# ADS7046_v6.net
KiCad netlist of a schematic drawn in EAGLE
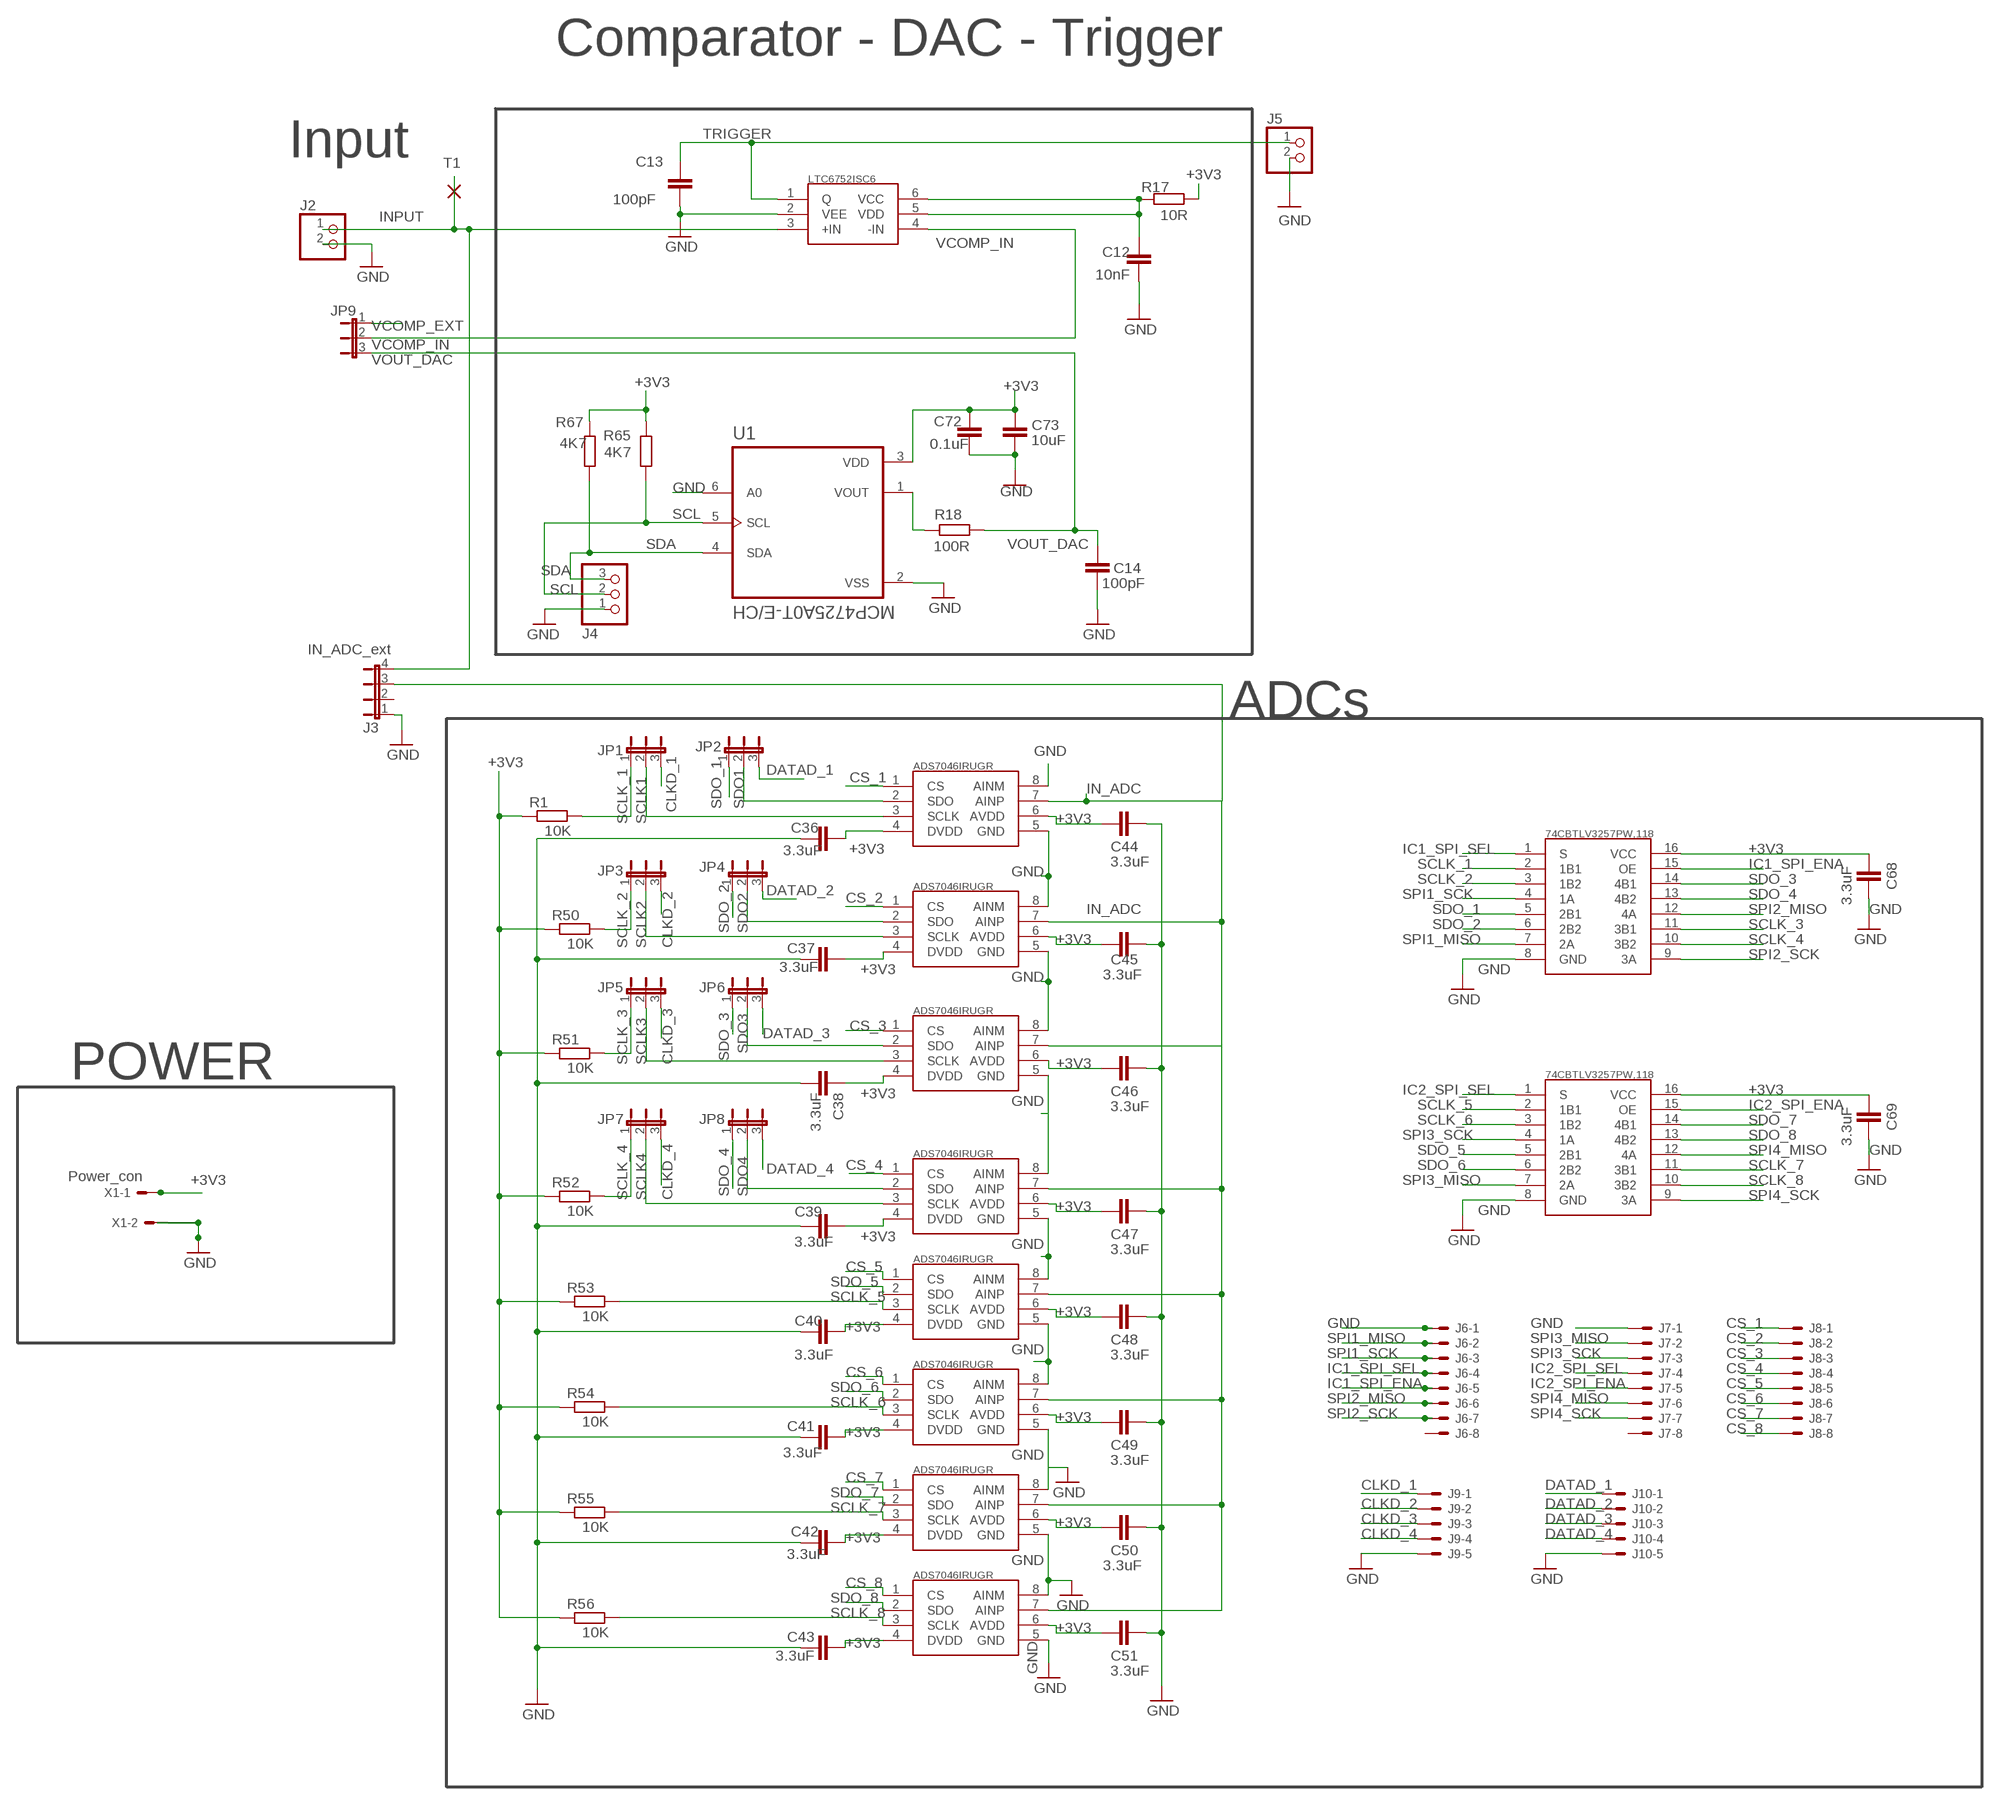
[diagram p0: schematic, sheet 1]

(export (version "E")
  (design (tool "Eeschema 10.0.6"))
  (components
    (comp (ref "C12")
      (value "10nF")
      (footprint "eagle-import:C1206")
      (libsource (lib "eagle-import") (part "C-EUC1206"))
    )
    (comp (ref "C13")
      (value "100pF")
      (footprint "eagle-import:C1206")
      (libsource (lib "eagle-import") (part "C-EUC1206"))
    )
    (comp (ref "C14")
      (value "100pF")
      (footprint "eagle-import:C1206")
      (libsource (lib "eagle-import") (part "C-EUC1206"))
    )
    (comp (ref "C36")
      (value "3.3uF")
      (footprint "eagle-import:C0805")
      (libsource (lib "eagle-import") (part "C-EUC0805"))
    )
    (comp (ref "C37")
      (value "3.3uF")
      (footprint "eagle-import:C0805")
      (libsource (lib "eagle-import") (part "C-EUC0805"))
    )
    (comp (ref "C38")
      (value "3.3uF")
      (footprint "eagle-import:C0805")
      (libsource (lib "eagle-import") (part "C-EUC0805"))
    )
    (comp (ref "C39")
      (value "3.3uF")
      (footprint "eagle-import:C0805")
      (libsource (lib "eagle-import") (part "C-EUC0805"))
    )
    (comp (ref "C40")
      (value "3.3uF")
      (footprint "eagle-import:C0805")
      (libsource (lib "eagle-import") (part "C-EUC0805"))
    )
    (comp (ref "C41")
      (value "3.3uF")
      (footprint "eagle-import:C0805")
      (libsource (lib "eagle-import") (part "C-EUC0805"))
    )
    (comp (ref "C42")
      (value "3.3uF")
      (footprint "eagle-import:C0805")
      (libsource (lib "eagle-import") (part "C-EUC0805"))
    )
    (comp (ref "C43")
      (value "3.3uF")
      (footprint "eagle-import:C0805")
      (libsource (lib "eagle-import") (part "C-EUC0805"))
    )
    (comp (ref "C44")
      (value "3.3uF")
      (footprint "eagle-import:C0805")
      (libsource (lib "eagle-import") (part "C-EUC0805"))
    )
    (comp (ref "C45")
      (value "3.3uF")
      (footprint "eagle-import:C0805")
      (libsource (lib "eagle-import") (part "C-EUC0805"))
    )
    (comp (ref "C46")
      (value "3.3uF")
      (footprint "eagle-import:C0805")
      (libsource (lib "eagle-import") (part "C-EUC0805"))
    )
    (comp (ref "C47")
      (value "3.3uF")
      (footprint "eagle-import:C0805")
      (libsource (lib "eagle-import") (part "C-EUC0805"))
    )
    (comp (ref "C48")
      (value "3.3uF")
      (footprint "eagle-import:C0805")
      (libsource (lib "eagle-import") (part "C-EUC0805"))
    )
    (comp (ref "C49")
      (value "3.3uF")
      (footprint "eagle-import:C0805")
      (libsource (lib "eagle-import") (part "C-EUC0805"))
    )
    (comp (ref "C50")
      (value "3.3uF")
      (footprint "eagle-import:C0805")
      (libsource (lib "eagle-import") (part "C-EUC0805"))
    )
    (comp (ref "C51")
      (value "3.3uF")
      (footprint "eagle-import:C0805")
      (libsource (lib "eagle-import") (part "C-EUC0805"))
    )
    (comp (ref "C68")
      (value "3.3uF")
      (footprint "eagle-import:C0805")
      (libsource (lib "eagle-import") (part "C-EUC0805"))
    )
    (comp (ref "C69")
      (value "3.3uF")
      (footprint "eagle-import:C0805")
      (libsource (lib "eagle-import") (part "C-EUC0805"))
    )
    (comp (ref "C72")
      (value "0.1uF")
      (footprint "eagle-import:C0805")
      (libsource (lib "eagle-import") (part "C-EUC0805"))
    )
    (comp (ref "C73")
      (value "10uF")
      (footprint "eagle-import:C0805")
      (libsource (lib "eagle-import") (part "C-EUC0805"))
    )
    (comp (ref "J2")
      (value "PINHD-1X2")
      (footprint "eagle-import:1X02")
      (libsource (lib "eagle-import") (part "PINHD-1X2"))
    )
    (comp (ref "J3")
      (value "IN_ADC_ext")
      (footprint "eagle-import:JP4")
      (libsource (lib "eagle-import") (part "JP4E"))
    )
    (comp (ref "J4")
      (value "PINHD-1X3")
      (footprint "eagle-import:1X03")
      (libsource (lib "eagle-import") (part "PINHD-1X3"))
    )
    (comp (ref "J5")
      (value "PINHD-1X2")
      (footprint "eagle-import:1X02")
      (libsource (lib "eagle-import") (part "PINHD-1X2"))
    )
    (comp (ref "J6")
      (value "22-27-2081-08")
      (footprint "eagle-import:6410-08")
      (fields (field (name "MF") "MOLEX"))
      (libsource (lib "eagle-import") (part "22-?-0827-2081"))
    )
    (comp (ref "J7")
      (value "22-27-2081-08")
      (footprint "eagle-import:6410-08")
      (fields (field (name "MF") "MOLEX"))
      (libsource (lib "eagle-import") (part "22-?-0827-2081"))
    )
    (comp (ref "J8")
      (value "22-27-2081-08")
      (footprint "eagle-import:6410-08")
      (fields (field (name "MF") "MOLEX"))
      (libsource (lib "eagle-import") (part "22-?-0827-2081"))
    )
    (comp (ref "J9")
      (value "22-27-2051-05")
      (footprint "eagle-import:6410-05")
      (fields (field (name "MF") "MOLEX"))
      (libsource (lib "eagle-import") (part "22-?-0527-2051"))
    )
    (comp (ref "J10")
      (value "22-27-2051-05")
      (footprint "eagle-import:6410-05")
      (fields (field (name "MF") "MOLEX"))
      (libsource (lib "eagle-import") (part "22-?-0527-2051"))
    )
    (comp (ref "JP1")
      (value "JP2E")
      (footprint "eagle-import:JP2")
      (libsource (lib "eagle-import") (part "JP2E"))
    )
    (comp (ref "JP2")
      (value "JP2E")
      (footprint "eagle-import:JP2")
      (libsource (lib "eagle-import") (part "JP2E"))
    )
    (comp (ref "JP3")
      (value "JP2E")
      (footprint "eagle-import:JP2")
      (libsource (lib "eagle-import") (part "JP2E"))
    )
    (comp (ref "JP4")
      (value "JP2E")
      (footprint "eagle-import:JP2")
      (libsource (lib "eagle-import") (part "JP2E"))
    )
    (comp (ref "JP5")
      (value "JP2E")
      (footprint "eagle-import:JP2")
      (libsource (lib "eagle-import") (part "JP2E"))
    )
    (comp (ref "JP6")
      (value "JP2E")
      (footprint "eagle-import:JP2")
      (libsource (lib "eagle-import") (part "JP2E"))
    )
    (comp (ref "JP7")
      (value "JP2E")
      (footprint "eagle-import:JP2")
      (libsource (lib "eagle-import") (part "JP2E"))
    )
    (comp (ref "JP8")
      (value "JP2E")
      (footprint "eagle-import:JP2")
      (libsource (lib "eagle-import") (part "JP2E"))
    )
    (comp (ref "JP9")
      (value "JP2E")
      (footprint "eagle-import:JP2")
      (libsource (lib "eagle-import") (part "JP2E"))
    )
    (comp (ref "R1")
      (value "10K")
      (footprint "eagle-import:R0805")
      (libsource (lib "eagle-import") (part "R-EU_R0805"))
    )
    (comp (ref "R17")
      (value "10R")
      (footprint "eagle-import:R1206")
      (libsource (lib "eagle-import") (part "R-EU_R1206"))
    )
    (comp (ref "R18")
      (value "100R")
      (footprint "eagle-import:R1206")
      (libsource (lib "eagle-import") (part "R-EU_R1206"))
    )
    (comp (ref "R50")
      (value "10K")
      (footprint "eagle-import:R0805")
      (libsource (lib "eagle-import") (part "R-EU_R0805"))
    )
    (comp (ref "R51")
      (value "10K")
      (footprint "eagle-import:R0805")
      (libsource (lib "eagle-import") (part "R-EU_R0805"))
    )
    (comp (ref "R52")
      (value "10K")
      (footprint "eagle-import:R0805")
      (libsource (lib "eagle-import") (part "R-EU_R0805"))
    )
    (comp (ref "R53")
      (value "10K")
      (footprint "eagle-import:R0805")
      (libsource (lib "eagle-import") (part "R-EU_R0805"))
    )
    (comp (ref "R54")
      (value "10K")
      (footprint "eagle-import:R0805")
      (libsource (lib "eagle-import") (part "R-EU_R0805"))
    )
    (comp (ref "R55")
      (value "10K")
      (footprint "eagle-import:R0805")
      (libsource (lib "eagle-import") (part "R-EU_R0805"))
    )
    (comp (ref "R56")
      (value "10K")
      (footprint "eagle-import:R0805")
      (libsource (lib "eagle-import") (part "R-EU_R0805"))
    )
    (comp (ref "R65")
      (value "4K7")
      (footprint "eagle-import:R0805")
      (libsource (lib "eagle-import") (part "R-EU_R0805"))
    )
    (comp (ref "R67")
      (value "4K7")
      (footprint "eagle-import:R0805")
      (libsource (lib "eagle-import") (part "R-EU_R0805"))
    )
    (comp (ref "T1")
      (value "WIREPADSMD1,27-254")
      (footprint "eagle-import:SMD1,27-2,54")
      (libsource (lib "eagle-import") (part "WIREPADSMD1,27-254"))
    )
    (comp (ref "U$2")
      (value "LTC6752ISC6")
      (footprint "eagle-import:LTC6752ISC6")
      (libsource (lib "eagle-import") (part "LTC6752ISC6"))
    )
    (comp (ref "U$12")
      (value "ADS7046IRUGR")
      (footprint "eagle-import:ADS7046IRUGR")
      (libsource (lib "eagle-import") (part "ADS7046IRUGR"))
    )
    (comp (ref "U$13")
      (value "ADS7046IRUGR")
      (footprint "eagle-import:ADS7046IRUGR")
      (libsource (lib "eagle-import") (part "ADS7046IRUGR"))
    )
    (comp (ref "U$14")
      (value "ADS7046IRUGR")
      (footprint "eagle-import:ADS7046IRUGR")
      (libsource (lib "eagle-import") (part "ADS7046IRUGR"))
    )
    (comp (ref "U$15")
      (value "ADS7046IRUGR")
      (footprint "eagle-import:ADS7046IRUGR")
      (libsource (lib "eagle-import") (part "ADS7046IRUGR"))
    )
    (comp (ref "U$16")
      (value "ADS7046IRUGR")
      (footprint "eagle-import:ADS7046IRUGR")
      (libsource (lib "eagle-import") (part "ADS7046IRUGR"))
    )
    (comp (ref "U$17")
      (value "ADS7046IRUGR")
      (footprint "eagle-import:ADS7046IRUGR")
      (libsource (lib "eagle-import") (part "ADS7046IRUGR"))
    )
    (comp (ref "U$18")
      (value "ADS7046IRUGR")
      (footprint "eagle-import:ADS7046IRUGR")
      (libsource (lib "eagle-import") (part "ADS7046IRUGR"))
    )
    (comp (ref "U$19")
      (value "ADS7046IRUGR")
      (footprint "eagle-import:ADS7046IRUGR")
      (libsource (lib "eagle-import") (part "ADS7046IRUGR"))
    )
    (comp (ref "U$28")
      (value "74CBTLV3257PW,118")
      (footprint "eagle-import:TSSOP16")
      (libsource (lib "eagle-import") (part "74CBTLV3257PW,118"))
    )
    (comp (ref "U$29")
      (value "74CBTLV3257PW,118")
      (footprint "eagle-import:TSSOP16")
      (libsource (lib "eagle-import") (part "74CBTLV3257PW,118"))
    )
    (comp (ref "U1")
      (value "MCP4725A0T-E/CH")
      (footprint "eagle-import:SOT95P270X145-6N")
      (fields (field (name "MF") "Microchip"))
      (libsource (lib "eagle-import") (part "MCP4725A0T-E/CH"))
    )
    (comp (ref "X1")
      (value "Power_con")
      (footprint "eagle-import:22-23-2021")
      (fields (field (name "MF") "MOLEX") (field (name "MPN") "22-23-2021"))
      (libsource (lib "eagle-import") (part "22-23-2021"))
    )
  )
  (nets
    (net (code "1") (name "/+3V3") (class "Default")
      (node (ref "C36") (pin "1") (pinfunction "1_1") (pintype "passive"))
      (node (ref "C37") (pin "1") (pinfunction "1_1") (pintype "passive"))
      (node (ref "C38") (pin "1") (pinfunction "1_1") (pintype "passive"))
      (node (ref "C39") (pin "1") (pinfunction "1_1") (pintype "passive"))
      (node (ref "C40") (pin "1") (pinfunction "1_1") (pintype "passive"))
      (node (ref "C41") (pin "1") (pinfunction "1_1") (pintype "passive"))
      (node (ref "C42") (pin "1") (pinfunction "1_1") (pintype "passive"))
      (node (ref "C43") (pin "1") (pinfunction "1_1") (pintype "passive"))
      (node (ref "C44") (pin "2") (pinfunction "2_2") (pintype "passive"))
      (node (ref "C45") (pin "2") (pinfunction "2_2") (pintype "passive"))
      (node (ref "C46") (pin "2") (pinfunction "2_2") (pintype "passive"))
      (node (ref "C47") (pin "2") (pinfunction "2_2") (pintype "passive"))
      (node (ref "C48") (pin "2") (pinfunction "2_2") (pintype "passive"))
      (node (ref "C49") (pin "2") (pinfunction "2_2") (pintype "passive"))
      (node (ref "C50") (pin "2") (pinfunction "2_2") (pintype "passive"))
      (node (ref "C51") (pin "2") (pinfunction "2_2") (pintype "passive"))
      (node (ref "C68") (pin "1") (pinfunction "1_1") (pintype "passive"))
      (node (ref "C69") (pin "1") (pinfunction "1_1") (pintype "passive"))
      (node (ref "C72") (pin "1") (pinfunction "1_1") (pintype "passive"))
      (node (ref "C73") (pin "1") (pinfunction "1_1") (pintype "passive"))
      (node (ref "R1") (pin "1") (pinfunction "1_1") (pintype "passive"))
      (node (ref "R17") (pin "1") (pinfunction "1_1") (pintype "passive"))
      (node (ref "R50") (pin "1") (pinfunction "1_1") (pintype "passive"))
      (node (ref "R51") (pin "1") (pinfunction "1_1") (pintype "passive"))
      (node (ref "R52") (pin "1") (pinfunction "1_1") (pintype "passive"))
      (node (ref "R53") (pin "1") (pinfunction "1_1") (pintype "passive"))
      (node (ref "R54") (pin "1") (pinfunction "1_1") (pintype "passive"))
      (node (ref "R55") (pin "1") (pinfunction "1_1") (pintype "passive"))
      (node (ref "R56") (pin "1") (pinfunction "1_1") (pintype "passive"))
      (node (ref "R65") (pin "2") (pinfunction "2_2") (pintype "passive"))
      (node (ref "R67") (pin "1") (pinfunction "1_1") (pintype "passive"))
      (node (ref "U$12") (pin "4") (pinfunction "DVDD_4") (pintype "bidirectional"))
      (node (ref "U$12") (pin "6") (pinfunction "AVDD_6") (pintype "bidirectional"))
      (node (ref "U$13") (pin "4") (pinfunction "DVDD_4") (pintype "bidirectional"))
      (node (ref "U$13") (pin "6") (pinfunction "AVDD_6") (pintype "bidirectional"))
      (node (ref "U$14") (pin "4") (pinfunction "DVDD_4") (pintype "bidirectional"))
      (node (ref "U$14") (pin "6") (pinfunction "AVDD_6") (pintype "bidirectional"))
      (node (ref "U$15") (pin "4") (pinfunction "DVDD_4") (pintype "bidirectional"))
      (node (ref "U$15") (pin "6") (pinfunction "AVDD_6") (pintype "bidirectional"))
      (node (ref "U$16") (pin "4") (pinfunction "DVDD_4") (pintype "bidirectional"))
      (node (ref "U$16") (pin "6") (pinfunction "AVDD_6") (pintype "bidirectional"))
      (node (ref "U$17") (pin "4") (pinfunction "DVDD_4") (pintype "bidirectional"))
      (node (ref "U$17") (pin "6") (pinfunction "AVDD_6") (pintype "bidirectional"))
      (node (ref "U$18") (pin "4") (pinfunction "DVDD_4") (pintype "bidirectional"))
      (node (ref "U$18") (pin "6") (pinfunction "AVDD_6") (pintype "bidirectional"))
      (node (ref "U$19") (pin "4") (pinfunction "DVDD_4") (pintype "bidirectional"))
      (node (ref "U$19") (pin "6") (pinfunction "AVDD_6") (pintype "bidirectional"))
      (node (ref "U$28") (pin "16") (pinfunction "VCC_16") (pintype "bidirectional"))
      (node (ref "U$29") (pin "16") (pinfunction "VCC_16") (pintype "bidirectional"))
      (node (ref "U1") (pin "3") (pinfunction "VDD_3") (pintype "power_in"))
      (node (ref "X1") (pin "1") (pinfunction "S_1") (pintype "passive"))
    )
    (net (code "2") (name "/CLKD_1") (class "Default")
      (node (ref "J9") (pin "1") (pinfunction "S_1") (pintype "passive"))
      (node (ref "JP1") (pin "3") (pinfunction "3_3") (pintype "passive"))
    )
    (net (code "3") (name "/CLKD_2") (class "Default")
      (node (ref "J9") (pin "2") (pinfunction "S_2") (pintype "passive"))
      (node (ref "JP3") (pin "3") (pinfunction "3_3") (pintype "passive"))
    )
    (net (code "4") (name "/CLKD_3") (class "Default")
      (node (ref "J9") (pin "3") (pinfunction "S_3") (pintype "passive"))
      (node (ref "JP5") (pin "3") (pinfunction "3_3") (pintype "passive"))
    )
    (net (code "5") (name "/CLKD_4") (class "Default")
      (node (ref "J9") (pin "4") (pinfunction "S_4") (pintype "passive"))
      (node (ref "JP7") (pin "3") (pinfunction "3_3") (pintype "passive"))
    )
    (net (code "6") (name "/CS_1") (class "Default")
      (node (ref "J8") (pin "1") (pinfunction "S_1") (pintype "passive"))
      (node (ref "U$12") (pin "1") (pinfunction "CS_1") (pintype "bidirectional"))
    )
    (net (code "7") (name "/CS_2") (class "Default")
      (node (ref "J8") (pin "2") (pinfunction "S_2") (pintype "passive"))
      (node (ref "U$13") (pin "1") (pinfunction "CS_1") (pintype "bidirectional"))
    )
    (net (code "8") (name "/CS_3") (class "Default")
      (node (ref "J8") (pin "3") (pinfunction "S_3") (pintype "passive"))
      (node (ref "U$14") (pin "1") (pinfunction "CS_1") (pintype "bidirectional"))
    )
    (net (code "9") (name "/CS_4") (class "Default")
      (node (ref "J8") (pin "4") (pinfunction "S_4") (pintype "passive"))
      (node (ref "U$15") (pin "1") (pinfunction "CS_1") (pintype "bidirectional"))
    )
    (net (code "10") (name "/CS_5") (class "Default")
      (node (ref "J8") (pin "5") (pinfunction "S_5") (pintype "passive"))
      (node (ref "U$16") (pin "1") (pinfunction "CS_1") (pintype "bidirectional"))
    )
    (net (code "11") (name "/CS_6") (class "Default")
      (node (ref "J8") (pin "6") (pinfunction "S_6") (pintype "passive"))
      (node (ref "U$17") (pin "1") (pinfunction "CS_1") (pintype "bidirectional"))
    )
    (net (code "12") (name "/CS_7") (class "Default")
      (node (ref "J8") (pin "7") (pinfunction "S_7") (pintype "passive"))
      (node (ref "U$18") (pin "1") (pinfunction "CS_1") (pintype "bidirectional"))
    )
    (net (code "13") (name "/CS_8") (class "Default")
      (node (ref "J8") (pin "8") (pinfunction "S_8") (pintype "passive"))
      (node (ref "U$19") (pin "1") (pinfunction "CS_1") (pintype "bidirectional"))
    )
    (net (code "14") (name "/DATAD_1") (class "Default")
      (node (ref "J10") (pin "1") (pinfunction "S_1") (pintype "passive"))
      (node (ref "JP2") (pin "3") (pinfunction "3_3") (pintype "passive"))
    )
    (net (code "15") (name "/DATAD_2") (class "Default")
      (node (ref "J10") (pin "2") (pinfunction "S_2") (pintype "passive"))
      (node (ref "JP4") (pin "3") (pinfunction "3_3") (pintype "passive"))
    )
    (net (code "16") (name "/DATAD_3") (class "Default")
      (node (ref "J10") (pin "3") (pinfunction "S_3") (pintype "passive"))
      (node (ref "JP6") (pin "3") (pinfunction "3_3") (pintype "passive"))
    )
    (net (code "17") (name "/DATAD_4") (class "Default")
      (node (ref "J10") (pin "4") (pinfunction "S_4") (pintype "passive"))
      (node (ref "JP8") (pin "3") (pinfunction "3_3") (pintype "passive"))
    )
    (net (code "18") (name "/IC1_SPI_ENA") (class "Default")
      (node (ref "J6") (pin "5") (pinfunction "S_5") (pintype "passive"))
      (node (ref "U$28") (pin "15") (pinfunction "OE_15") (pintype "bidirectional"))
    )
    (net (code "19") (name "/IC1_SPI_SEL") (class "Default")
      (node (ref "J6") (pin "4") (pinfunction "S_4") (pintype "passive"))
      (node (ref "U$28") (pin "1") (pinfunction "S_1") (pintype "bidirectional"))
    )
    (net (code "20") (name "/IC2_SPI_ENA") (class "Default")
      (node (ref "J7") (pin "5") (pinfunction "S_5") (pintype "passive"))
      (node (ref "U$29") (pin "15") (pinfunction "OE_15") (pintype "bidirectional"))
    )
    (net (code "21") (name "/IC2_SPI_SEL") (class "Default")
      (node (ref "J7") (pin "4") (pinfunction "S_4") (pintype "passive"))
      (node (ref "U$29") (pin "1") (pinfunction "S_1") (pintype "bidirectional"))
    )
    (net (code "22") (name "/INPUT") (class "Default")
      (node (ref "J2") (pin "1") (pinfunction "1_1") (pintype "passive"))
      (node (ref "J3") (pin "4") (pinfunction "4_4") (pintype "passive"))
      (node (ref "T1") (pin "1") (pinfunction "P_1") (pintype "passive"))
      (node (ref "U$2") (pin "3") (pinfunction "+IN_3") (pintype "bidirectional"))
    )
    (net (code "23") (name "/IN_ADC") (class "Default")
      (node (ref "J3") (pin "3") (pinfunction "3_3") (pintype "passive"))
      (node (ref "U$12") (pin "7") (pinfunction "AINP_7") (pintype "bidirectional"))
      (node (ref "U$13") (pin "7") (pinfunction "AINP_7") (pintype "bidirectional"))
      (node (ref "U$14") (pin "7") (pinfunction "AINP_7") (pintype "bidirectional"))
      (node (ref "U$15") (pin "7") (pinfunction "AINP_7") (pintype "bidirectional"))
      (node (ref "U$16") (pin "7") (pinfunction "AINP_7") (pintype "bidirectional"))
      (node (ref "U$17") (pin "7") (pinfunction "AINP_7") (pintype "bidirectional"))
      (node (ref "U$18") (pin "7") (pinfunction "AINP_7") (pintype "bidirectional"))
      (node (ref "U$19") (pin "7") (pinfunction "AINP_7") (pintype "bidirectional"))
    )
    (net (code "24") (name "/SCL") (class "Default")
      (node (ref "J4") (pin "2") (pinfunction "2_2") (pintype "passive"))
      (node (ref "R65") (pin "1") (pinfunction "1_1") (pintype "passive"))
      (node (ref "U1") (pin "5") (pinfunction "SCL_5") (pintype "input"))
    )
    (net (code "25") (name "/SCLK1") (class "Default")
      (node (ref "JP1") (pin "2") (pinfunction "2_2") (pintype "passive"))
      (node (ref "U$12") (pin "3") (pinfunction "SCLK_3") (pintype "bidirectional"))
    )
    (net (code "26") (name "/SCLK2") (class "Default")
      (node (ref "JP3") (pin "2") (pinfunction "2_2") (pintype "passive"))
      (node (ref "U$13") (pin "3") (pinfunction "SCLK_3") (pintype "bidirectional"))
    )
    (net (code "27") (name "/SCLK3") (class "Default")
      (node (ref "JP5") (pin "2") (pinfunction "2_2") (pintype "passive"))
      (node (ref "U$14") (pin "3") (pinfunction "SCLK_3") (pintype "bidirectional"))
    )
    (net (code "28") (name "/SCLK4") (class "Default")
      (node (ref "JP7") (pin "2") (pinfunction "2_2") (pintype "passive"))
      (node (ref "U$15") (pin "3") (pinfunction "SCLK_3") (pintype "bidirectional"))
    )
    (net (code "29") (name "/SCLK_1") (class "Default")
      (node (ref "JP1") (pin "1") (pinfunction "1_1") (pintype "passive"))
      (node (ref "R1") (pin "2") (pinfunction "2_2") (pintype "passive"))
      (node (ref "U$28") (pin "2") (pinfunction "1B1_2") (pintype "bidirectional"))
    )
    (net (code "30") (name "/SCLK_2") (class "Default")
      (node (ref "JP3") (pin "1") (pinfunction "1_1") (pintype "passive"))
      (node (ref "R50") (pin "2") (pinfunction "2_2") (pintype "passive"))
      (node (ref "U$28") (pin "3") (pinfunction "1B2_3") (pintype "bidirectional"))
    )
    (net (code "31") (name "/SCLK_3") (class "Default")
      (node (ref "JP5") (pin "1") (pinfunction "1_1") (pintype "passive"))
      (node (ref "R51") (pin "2") (pinfunction "2_2") (pintype "passive"))
      (node (ref "U$28") (pin "11") (pinfunction "3B1_11") (pintype "bidirectional"))
    )
    (net (code "32") (name "/SCLK_4") (class "Default")
      (node (ref "JP7") (pin "1") (pinfunction "1_1") (pintype "passive"))
      (node (ref "R52") (pin "2") (pinfunction "2_2") (pintype "passive"))
      (node (ref "U$28") (pin "10") (pinfunction "3B2_10") (pintype "bidirectional"))
    )
    (net (code "33") (name "/SCLK_5") (class "Default")
      (node (ref "R53") (pin "2") (pinfunction "2_2") (pintype "passive"))
      (node (ref "U$16") (pin "3") (pinfunction "SCLK_3") (pintype "bidirectional"))
      (node (ref "U$29") (pin "2") (pinfunction "1B1_2") (pintype "bidirectional"))
    )
    (net (code "34") (name "/SCLK_6") (class "Default")
      (node (ref "R54") (pin "2") (pinfunction "2_2") (pintype "passive"))
      (node (ref "U$17") (pin "3") (pinfunction "SCLK_3") (pintype "bidirectional"))
      (node (ref "U$29") (pin "3") (pinfunction "1B2_3") (pintype "bidirectional"))
    )
    (net (code "35") (name "/SCLK_7") (class "Default")
      (node (ref "R55") (pin "2") (pinfunction "2_2") (pintype "passive"))
      (node (ref "U$18") (pin "3") (pinfunction "SCLK_3") (pintype "bidirectional"))
      (node (ref "U$29") (pin "11") (pinfunction "3B1_11") (pintype "bidirectional"))
    )
    (net (code "36") (name "/SCLK_8") (class "Default")
      (node (ref "R56") (pin "2") (pinfunction "2_2") (pintype "passive"))
      (node (ref "U$19") (pin "3") (pinfunction "SCLK_3") (pintype "bidirectional"))
      (node (ref "U$29") (pin "10") (pinfunction "3B2_10") (pintype "bidirectional"))
    )
    (net (code "37") (name "/SDA") (class "Default")
      (node (ref "J4") (pin "3") (pinfunction "3_3") (pintype "passive"))
      (node (ref "R67") (pin "2") (pinfunction "2_2") (pintype "passive"))
      (node (ref "U1") (pin "4") (pinfunction "SDA_4") (pintype "bidirectional"))
    )
    (net (code "38") (name "/SDO1") (class "Default")
      (node (ref "JP2") (pin "2") (pinfunction "2_2") (pintype "passive"))
      (node (ref "U$12") (pin "2") (pinfunction "SDO_2") (pintype "bidirectional"))
    )
    (net (code "39") (name "/SDO2") (class "Default")
      (node (ref "JP4") (pin "2") (pinfunction "2_2") (pintype "passive"))
      (node (ref "U$13") (pin "2") (pinfunction "SDO_2") (pintype "bidirectional"))
    )
    (net (code "40") (name "/SDO3") (class "Default")
      (node (ref "JP6") (pin "2") (pinfunction "2_2") (pintype "passive"))
      (node (ref "U$14") (pin "2") (pinfunction "SDO_2") (pintype "bidirectional"))
    )
    (net (code "41") (name "/SDO4") (class "Default")
      (node (ref "JP8") (pin "2") (pinfunction "2_2") (pintype "passive"))
      (node (ref "U$15") (pin "2") (pinfunction "SDO_2") (pintype "bidirectional"))
    )
    (net (code "42") (name "/SDO_1") (class "Default")
      (node (ref "JP2") (pin "1") (pinfunction "1_1") (pintype "passive"))
      (node (ref "U$28") (pin "5") (pinfunction "2B1_5") (pintype "bidirectional"))
    )
    (net (code "43") (name "/SDO_2") (class "Default")
      (node (ref "JP4") (pin "1") (pinfunction "1_1") (pintype "passive"))
      (node (ref "U$28") (pin "6") (pinfunction "2B2_6") (pintype "bidirectional"))
    )
    (net (code "44") (name "/SDO_3") (class "Default")
      (node (ref "JP6") (pin "1") (pinfunction "1_1") (pintype "passive"))
      (node (ref "U$28") (pin "14") (pinfunction "4B1_14") (pintype "bidirectional"))
    )
    (net (code "45") (name "/SDO_4") (class "Default")
      (node (ref "JP8") (pin "1") (pinfunction "1_1") (pintype "passive"))
      (node (ref "U$28") (pin "13") (pinfunction "4B2_13") (pintype "bidirectional"))
    )
    (net (code "46") (name "/SDO_5") (class "Default")
      (node (ref "U$16") (pin "2") (pinfunction "SDO_2") (pintype "bidirectional"))
      (node (ref "U$29") (pin "5") (pinfunction "2B1_5") (pintype "bidirectional"))
    )
    (net (code "47") (name "/SDO_6") (class "Default")
      (node (ref "U$17") (pin "2") (pinfunction "SDO_2") (pintype "bidirectional"))
      (node (ref "U$29") (pin "6") (pinfunction "2B2_6") (pintype "bidirectional"))
    )
    (net (code "48") (name "/SDO_7") (class "Default")
      (node (ref "U$18") (pin "2") (pinfunction "SDO_2") (pintype "bidirectional"))
      (node (ref "U$29") (pin "14") (pinfunction "4B1_14") (pintype "bidirectional"))
    )
    (net (code "49") (name "/SDO_8") (class "Default")
      (node (ref "U$19") (pin "2") (pinfunction "SDO_2") (pintype "bidirectional"))
      (node (ref "U$29") (pin "13") (pinfunction "4B2_13") (pintype "bidirectional"))
    )
    (net (code "50") (name "/SPI1_MISO") (class "Default")
      (node (ref "J6") (pin "2") (pinfunction "S_2") (pintype "passive"))
      (node (ref "U$28") (pin "7") (pinfunction "2A_7") (pintype "bidirectional"))
    )
    (net (code "51") (name "/SPI1_SCK") (class "Default")
      (node (ref "J6") (pin "3") (pinfunction "S_3") (pintype "passive"))
      (node (ref "U$28") (pin "4") (pinfunction "1A_4") (pintype "bidirectional"))
    )
    (net (code "52") (name "/SPI2_MISO") (class "Default")
      (node (ref "J6") (pin "6") (pinfunction "S_6") (pintype "passive"))
      (node (ref "U$28") (pin "12") (pinfunction "4A_12") (pintype "bidirectional"))
    )
    (net (code "53") (name "/SPI2_SCK") (class "Default")
      (node (ref "J6") (pin "7") (pinfunction "S_7") (pintype "passive"))
      (node (ref "U$28") (pin "9") (pinfunction "3A_9") (pintype "bidirectional"))
    )
    (net (code "54") (name "/SPI3_MISO") (class "Default")
      (node (ref "J7") (pin "2") (pinfunction "S_2") (pintype "passive"))
      (node (ref "U$29") (pin "7") (pinfunction "2A_7") (pintype "bidirectional"))
    )
    (net (code "55") (name "/SPI3_SCK") (class "Default")
      (node (ref "J7") (pin "3") (pinfunction "S_3") (pintype "passive"))
      (node (ref "U$29") (pin "4") (pinfunction "1A_4") (pintype "bidirectional"))
    )
    (net (code "56") (name "/SPI4_MISO") (class "Default")
      (node (ref "J7") (pin "6") (pinfunction "S_6") (pintype "passive"))
      (node (ref "U$29") (pin "12") (pinfunction "4A_12") (pintype "bidirectional"))
    )
    (net (code "57") (name "/SPI4_SCK") (class "Default")
      (node (ref "J7") (pin "7") (pinfunction "S_7") (pintype "passive"))
      (node (ref "U$29") (pin "9") (pinfunction "3A_9") (pintype "bidirectional"))
    )
    (net (code "58") (name "/TRIGGER") (class "Default")
      (node (ref "C13") (pin "1") (pinfunction "1_1") (pintype "passive"))
      (node (ref "J5") (pin "1") (pinfunction "1_1") (pintype "passive"))
      (node (ref "U$2") (pin "1") (pinfunction "Q_1") (pintype "bidirectional"))
    )
    (net (code "59") (name "/VCOMP_EXT") (class "Default")
      (node (ref "JP9") (pin "1") (pinfunction "1_1") (pintype "passive"))
    )
    (net (code "60") (name "/VCOMP_IN") (class "Default")
      (node (ref "JP9") (pin "2") (pinfunction "2_2") (pintype "passive"))
      (node (ref "U$2") (pin "4") (pinfunction "-IN_4") (pintype "bidirectional"))
    )
    (net (code "61") (name "/VOUT_DAC") (class "Default")
      (node (ref "C14") (pin "1") (pinfunction "1_1") (pintype "passive"))
      (node (ref "JP9") (pin "3") (pinfunction "3_3") (pintype "passive"))
      (node (ref "R18") (pin "1") (pinfunction "1_1") (pintype "passive"))
    )
    (net (code "62") (name "GND") (class "Default")
      (node (ref "C12") (pin "2") (pinfunction "2_2") (pintype "passive"))
      (node (ref "C13") (pin "2") (pinfunction "2_2") (pintype "passive"))
      (node (ref "C14") (pin "2") (pinfunction "2_2") (pintype "passive"))
      (node (ref "C36") (pin "2") (pinfunction "2_2") (pintype "passive"))
      (node (ref "C37") (pin "2") (pinfunction "2_2") (pintype "passive"))
      (node (ref "C38") (pin "2") (pinfunction "2_2") (pintype "passive"))
      (node (ref "C39") (pin "2") (pinfunction "2_2") (pintype "passive"))
      (node (ref "C40") (pin "2") (pinfunction "2_2") (pintype "passive"))
      (node (ref "C41") (pin "2") (pinfunction "2_2") (pintype "passive"))
      (node (ref "C42") (pin "2") (pinfunction "2_2") (pintype "passive"))
      (node (ref "C43") (pin "2") (pinfunction "2_2") (pintype "passive"))
      (node (ref "C44") (pin "1") (pinfunction "1_1") (pintype "passive"))
      (node (ref "C45") (pin "1") (pinfunction "1_1") (pintype "passive"))
      (node (ref "C46") (pin "1") (pinfunction "1_1") (pintype "passive"))
      (node (ref "C47") (pin "1") (pinfunction "1_1") (pintype "passive"))
      (node (ref "C48") (pin "1") (pinfunction "1_1") (pintype "passive"))
      (node (ref "C49") (pin "1") (pinfunction "1_1") (pintype "passive"))
      (node (ref "C50") (pin "1") (pinfunction "1_1") (pintype "passive"))
      (node (ref "C51") (pin "1") (pinfunction "1_1") (pintype "passive"))
      (node (ref "C68") (pin "2") (pinfunction "2_2") (pintype "passive"))
      (node (ref "C69") (pin "2") (pinfunction "2_2") (pintype "passive"))
      (node (ref "C72") (pin "2") (pinfunction "2_2") (pintype "passive"))
      (node (ref "C73") (pin "2") (pinfunction "2_2") (pintype "passive"))
      (node (ref "J10") (pin "5") (pinfunction "S_5") (pintype "passive"))
      (node (ref "J2") (pin "2") (pinfunction "2_2") (pintype "passive"))
      (node (ref "J3") (pin "1") (pinfunction "1_1") (pintype "passive"))
      (node (ref "J4") (pin "1") (pinfunction "1_1") (pintype "passive"))
      (node (ref "J5") (pin "2") (pinfunction "2_2") (pintype "passive"))
      (node (ref "J6") (pin "1") (pinfunction "S_1") (pintype "passive"))
      (node (ref "J7") (pin "1") (pinfunction "S_1") (pintype "passive"))
      (node (ref "J9") (pin "5") (pinfunction "S_5") (pintype "passive"))
      (node (ref "U$12") (pin "5") (pinfunction "GND_5") (pintype "bidirectional"))
      (node (ref "U$12") (pin "8") (pinfunction "AINM_8") (pintype "bidirectional"))
      (node (ref "U$13") (pin "5") (pinfunction "GND_5") (pintype "bidirectional"))
      (node (ref "U$13") (pin "8") (pinfunction "AINM_8") (pintype "bidirectional"))
      (node (ref "U$14") (pin "5") (pinfunction "GND_5") (pintype "bidirectional"))
      (node (ref "U$14") (pin "8") (pinfunction "AINM_8") (pintype "bidirectional"))
      (node (ref "U$15") (pin "5") (pinfunction "GND_5") (pintype "bidirectional"))
      (node (ref "U$15") (pin "8") (pinfunction "AINM_8") (pintype "bidirectional"))
      (node (ref "U$16") (pin "5") (pinfunction "GND_5") (pintype "bidirectional"))
      (node (ref "U$16") (pin "8") (pinfunction "AINM_8") (pintype "bidirectional"))
      (node (ref "U$17") (pin "5") (pinfunction "GND_5") (pintype "bidirectional"))
      (node (ref "U$17") (pin "8") (pinfunction "AINM_8") (pintype "bidirectional"))
      (node (ref "U$18") (pin "5") (pinfunction "GND_5") (pintype "bidirectional"))
      (node (ref "U$18") (pin "8") (pinfunction "AINM_8") (pintype "bidirectional"))
      (node (ref "U$19") (pin "5") (pinfunction "GND_5") (pintype "bidirectional"))
      (node (ref "U$19") (pin "8") (pinfunction "AINM_8") (pintype "bidirectional"))
      (node (ref "U$2") (pin "2") (pinfunction "VEE_2") (pintype "bidirectional"))
      (node (ref "U$28") (pin "8") (pinfunction "GND_8") (pintype "bidirectional"))
      (node (ref "U$29") (pin "8") (pinfunction "GND_8") (pintype "bidirectional"))
      (node (ref "U1") (pin "2") (pinfunction "VSS_2") (pintype "power_in"))
      (node (ref "U1") (pin "6") (pinfunction "A0_6") (pintype "input"))
      (node (ref "X1") (pin "2") (pinfunction "S_2") (pintype "passive"))
    )
    (net (code "63") (name "Net-(U$2-VCC)") (class "Default")
      (node (ref "C12") (pin "1") (pinfunction "1_1") (pintype "passive"))
      (node (ref "R17") (pin "2") (pinfunction "2_2") (pintype "passive"))
      (node (ref "U$2") (pin "5") (pinfunction "VDD_5") (pintype "bidirectional"))
      (node (ref "U$2") (pin "6") (pinfunction "VCC_6") (pintype "bidirectional"))
    )
    (net (code "64") (name "Net-(U1-VOUT)") (class "Default")
      (node (ref "R18") (pin "2") (pinfunction "2_2") (pintype "passive"))
      (node (ref "U1") (pin "1") (pinfunction "VOUT_1") (pintype "output"))
    )
    (net (code "65") (name "unconnected-(J3-Pad2)") (class "Default")
      (node (ref "J3") (pin "2") (pinfunction "2_2") (pintype "passive"))
    )
    (net (code "66") (name "unconnected-(J6H-S-Pad8)") (class "Default")
      (node (ref "J6") (pin "8") (pinfunction "S_8") (pintype "passive"))
    )
    (net (code "67") (name "unconnected-(J7H-S-Pad8)") (class "Default")
      (node (ref "J7") (pin "8") (pinfunction "S_8") (pintype "passive"))
    )
  )
)
